# psu.net
KiCad netlist of a schematic drawn in EAGLE
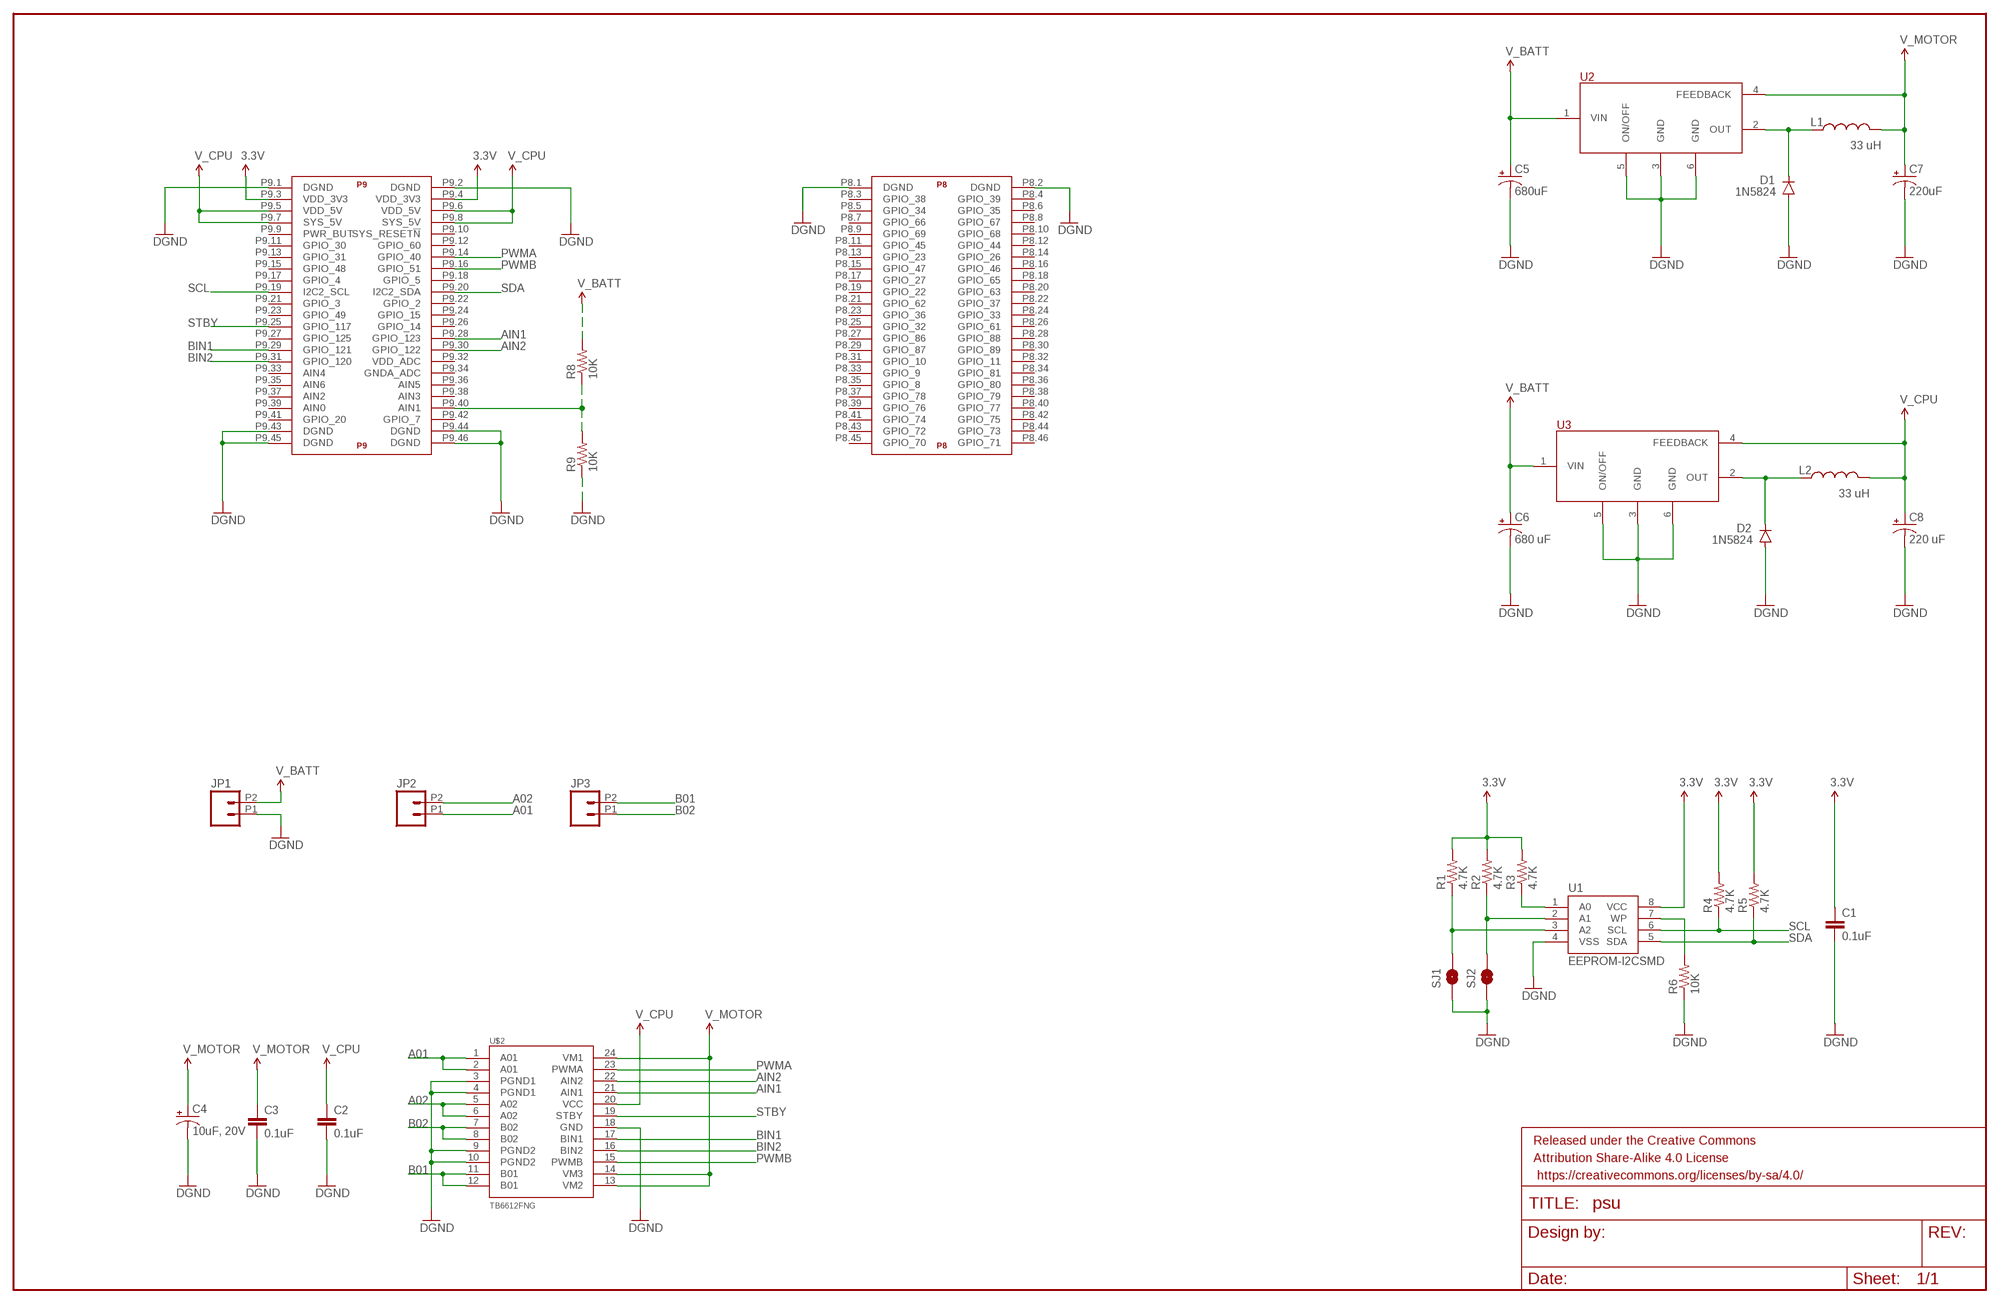
[diagram p0: schematic, sheet 1]

(export (version "E")
  (design (tool "Eeschema 10.0.6"))
  (components
    (comp (ref "C1")
      (value "0.1uF")
      (footprint "eagle-import:0603-CAP")
      (libsource (lib "eagle-import") (part "0.1UF-25V(+80/-20%)(0603)"))
    )
    (comp (ref "C2")
      (value "0.1uF")
      (footprint "eagle-import:0603-CAP")
      (libsource (lib "eagle-import") (part "0.1UF-25V(+80/-20%)(0603)"))
    )
    (comp (ref "C3")
      (value "0.1uF")
      (footprint "eagle-import:0603-CAP")
      (libsource (lib "eagle-import") (part "0.1UF-25V(+80/-20%)(0603)"))
    )
    (comp (ref "C4")
      (value "10uF, 20V")
      (footprint "eagle-import:CPOL-RADIAL-10UF-25V-KIT")
      (libsource (lib "eagle-import") (part "10UF-25V-20%(PTH)KIT"))
    )
    (comp (ref "C5")
      (value "680uF")
      (footprint "eagle-import:CPOL-RADIAL-10UF-25V")
      (libsource (lib "eagle-import") (part "CAP_POLPTH2"))
    )
    (comp (ref "C6")
      (value "680 uF")
      (footprint "eagle-import:CPOL-RADIAL-10UF-25V")
      (libsource (lib "eagle-import") (part "CAP_POLPTH2"))
    )
    (comp (ref "C7")
      (value "220uF")
      (footprint "eagle-import:CPOL-RADIAL-10UF-25V")
      (libsource (lib "eagle-import") (part "CAP_POLPTH2"))
    )
    (comp (ref "C8")
      (value "220 uF")
      (footprint "eagle-import:CPOL-RADIAL-10UF-25V")
      (libsource (lib "eagle-import") (part "CAP_POLPTH2"))
    )
    (comp (ref "D1")
      (value "1N5824")
      (footprint "eagle-import:DIODE-1N4001")
      (libsource (lib "eagle-import") (part "DIODEPTH"))
    )
    (comp (ref "D2")
      (value "1N5824")
      (footprint "eagle-import:DIODE-1N4001")
      (libsource (lib "eagle-import") (part "DIODEPTH"))
    )
    (comp (ref "FRAME2")
      (value "FRAME-LEDGER")
      (footprint "eagle-import:CREATIVE_COMMONS")
      (libsource (lib "eagle-import") (part "FRAME-LEDGER"))
    )
    (comp (ref "JP1")
      (value "M022.54MM_SCREWTERM")
      (footprint "eagle-import:1X02_2.54_SCREWTERM")
      (libsource (lib "eagle-import") (part "M022.54MM_SCREWTERM"))
    )
    (comp (ref "JP2")
      (value "M022.54MM_SCREWTERM")
      (footprint "eagle-import:1X02_2.54_SCREWTERM")
      (libsource (lib "eagle-import") (part "M022.54MM_SCREWTERM"))
    )
    (comp (ref "JP3")
      (value "M022.54MM_SCREWTERM")
      (footprint "eagle-import:1X02_2.54_SCREWTERM")
      (libsource (lib "eagle-import") (part "M022.54MM_SCREWTERM"))
    )
    (comp (ref "L1")
      (value "33 uH")
      (footprint "eagle-import:0603")
      (libsource (lib "eagle-import") (part "INDUCTOR0603"))
    )
    (comp (ref "L2")
      (value "33 uH")
      (footprint "eagle-import:0603")
      (libsource (lib "eagle-import") (part "INDUCTOR0603"))
    )
    (comp (ref "R1")
      (value "4.7K")
      (footprint "eagle-import:0603-RES")
      (libsource (lib "eagle-import") (part "4.7KOHM-1/10W-1%(0603)"))
    )
    (comp (ref "R2")
      (value "4.7K")
      (footprint "eagle-import:0603-RES")
      (libsource (lib "eagle-import") (part "4.7KOHM-1/10W-1%(0603)"))
    )
    (comp (ref "R3")
      (value "4.7K")
      (footprint "eagle-import:0603-RES")
      (libsource (lib "eagle-import") (part "4.7KOHM-1/10W-1%(0603)"))
    )
    (comp (ref "R4")
      (value "4.7K")
      (footprint "eagle-import:0603-RES")
      (libsource (lib "eagle-import") (part "4.7KOHM-1/10W-1%(0603)"))
    )
    (comp (ref "R5")
      (value "4.7K")
      (footprint "eagle-import:0603-RES")
      (libsource (lib "eagle-import") (part "4.7KOHM-1/10W-1%(0603)"))
    )
    (comp (ref "R6")
      (value "10K")
      (footprint "eagle-import:0603-RES")
      (libsource (lib "eagle-import") (part "10KOHM-1/10W-1%(0603)0603"))
    )
    (comp (ref "R8")
      (value "10K")
      (footprint "eagle-import:0603-RES")
      (libsource (lib "eagle-import") (part "10KOHM-1/10W-1%(0603)0603"))
    )
    (comp (ref "R9")
      (value "10K")
      (footprint "eagle-import:0603-RES")
      (libsource (lib "eagle-import") (part "10KOHM-1/10W-1%(0603)0603"))
    )
    (comp (ref "SJ1")
      (value "JUMPER-PAD-2-NO")
      (footprint "eagle-import:PAD-JUMPER-2-NO_NO_SILK")
      (libsource (lib "eagle-import") (part "JUMPER-PAD-2-NO"))
    )
    (comp (ref "SJ2")
      (value "JUMPER-PAD-2-NO")
      (footprint "eagle-import:PAD-JUMPER-2-NO_NO_SILK")
      (libsource (lib "eagle-import") (part "JUMPER-PAD-2-NO"))
    )
    (comp (ref "U$1")
      (value "BEAGLE_BONE_BLACK_CAPE")
      (footprint "eagle-import:BEAGLE_BONE_BLACK_CAPE")
      (libsource (lib "eagle-import") (part "BEAGLE_BONE_BLACK_CAPE"))
    )
    (comp (ref "U$2")
      (value "TB6612FNG")
      (footprint "eagle-import:SSOP24")
      (libsource (lib "eagle-import") (part "TB6612FNG"))
    )
    (comp (ref "U1")
      (value "EEPROM-I2CSMD")
      (footprint "eagle-import:SO08")
      (libsource (lib "eagle-import") (part "EEPROM-I2CSMD"))
    )
    (comp (ref "U2")
      (value "LM2596")
      (footprint "eagle-import:TO-263")
      (libsource (lib "eagle-import") (part "LM2596"))
    )
    (comp (ref "U3")
      (value "LM2596")
      (footprint "eagle-import:TO-263")
      (libsource (lib "eagle-import") (part "LM2596"))
    )
  )
  (nets
    (net (code "1") (name "/A01") (class "Default")
      (node (ref "JP2") (pin "P1") (pinfunction "1_P1") (pintype "passive"))
      (node (ref "U$2") (pin "1") (pinfunction "A01_1") (pintype "bidirectional"))
      (node (ref "U$2") (pin "2") (pinfunction "A01_2") (pintype "bidirectional"))
    )
    (net (code "2") (name "/A02") (class "Default")
      (node (ref "JP2") (pin "P2") (pinfunction "2_P2") (pintype "passive"))
      (node (ref "U$2") (pin "5") (pinfunction "A02_5") (pintype "bidirectional"))
      (node (ref "U$2") (pin "6") (pinfunction "A02_6") (pintype "bidirectional"))
    )
    (net (code "3") (name "/AIN1") (class "Default")
      (node (ref "U$1") (pin "P9.28") (pinfunction "GPIO_123_P9.28") (pintype "bidirectional"))
      (node (ref "U$2") (pin "21") (pinfunction "AIN1_21") (pintype "bidirectional"))
    )
    (net (code "4") (name "/AIN2") (class "Default")
      (node (ref "U$1") (pin "P9.30") (pinfunction "GPIO_122_P9.30") (pintype "bidirectional"))
      (node (ref "U$2") (pin "22") (pinfunction "AIN2_22") (pintype "bidirectional"))
    )
    (net (code "5") (name "/B01") (class "Default")
      (node (ref "JP3") (pin "P2") (pinfunction "2_P2") (pintype "passive"))
      (node (ref "U$2") (pin "11") (pinfunction "B01_11") (pintype "bidirectional"))
      (node (ref "U$2") (pin "12") (pinfunction "B01_12") (pintype "bidirectional"))
    )
    (net (code "6") (name "/B02") (class "Default")
      (node (ref "JP3") (pin "P1") (pinfunction "1_P1") (pintype "passive"))
      (node (ref "U$2") (pin "7") (pinfunction "B02_7") (pintype "bidirectional"))
      (node (ref "U$2") (pin "8") (pinfunction "B02_8") (pintype "bidirectional"))
    )
    (net (code "7") (name "/BIN1") (class "Default")
      (node (ref "U$1") (pin "P9.29") (pinfunction "GPIO_121_P9.29") (pintype "bidirectional"))
      (node (ref "U$2") (pin "17") (pinfunction "BIN1_17") (pintype "bidirectional"))
    )
    (net (code "8") (name "/BIN2") (class "Default")
      (node (ref "U$1") (pin "P9.31") (pinfunction "GPIO_120_P9.31") (pintype "bidirectional"))
      (node (ref "U$2") (pin "16") (pinfunction "BIN2_16") (pintype "bidirectional"))
    )
    (net (code "9") (name "/PWMA") (class "Default")
      (node (ref "U$1") (pin "P9.14") (pinfunction "GPIO_40_P9.14") (pintype "bidirectional"))
      (node (ref "U$2") (pin "23") (pinfunction "PWMA_23") (pintype "bidirectional"))
    )
    (net (code "10") (name "/PWMB") (class "Default")
      (node (ref "U$1") (pin "P9.16") (pinfunction "GPIO_51_P9.16") (pintype "bidirectional"))
      (node (ref "U$2") (pin "15") (pinfunction "PWMB_15") (pintype "bidirectional"))
    )
    (net (code "11") (name "/SCL") (class "Default")
      (node (ref "R4") (pin "1") (pinfunction "1_1") (pintype "passive"))
      (node (ref "U$1") (pin "P9.19") (pinfunction "I2C2_SCL_P9.19") (pintype "bidirectional"))
      (node (ref "U1") (pin "6") (pinfunction "SCL_6") (pintype "bidirectional"))
    )
    (net (code "12") (name "/SDA") (class "Default")
      (node (ref "R5") (pin "1") (pinfunction "1_1") (pintype "passive"))
      (node (ref "U$1") (pin "P9.20") (pinfunction "I2C2_SDA_P9.20") (pintype "bidirectional"))
      (node (ref "U1") (pin "5") (pinfunction "SDA_5") (pintype "bidirectional"))
    )
    (net (code "13") (name "/STBY") (class "Default")
      (node (ref "U$1") (pin "P9.25") (pinfunction "GPIO_117_P9.25") (pintype "bidirectional"))
      (node (ref "U$2") (pin "19") (pinfunction "STBY_19") (pintype "bidirectional"))
    )
    (net (code "14") (name "3.3V") (class "Default")
      (node (ref "C1") (pin "1") (pinfunction "1_1") (pintype "passive"))
      (node (ref "R1") (pin "2") (pinfunction "2_2") (pintype "passive"))
      (node (ref "R2") (pin "2") (pinfunction "2_2") (pintype "passive"))
      (node (ref "R3") (pin "2") (pinfunction "2_2") (pintype "passive"))
      (node (ref "R4") (pin "2") (pinfunction "2_2") (pintype "passive"))
      (node (ref "R5") (pin "2") (pinfunction "2_2") (pintype "passive"))
      (node (ref "U$1") (pin "P9.3") (pinfunction "VDD_3V3_P9.3") (pintype "bidirectional"))
      (node (ref "U$1") (pin "P9.4") (pinfunction "VDD_3V3_P9.4") (pintype "bidirectional"))
      (node (ref "U1") (pin "8") (pinfunction "VCC_8") (pintype "power_in"))
    )
    (net (code "15") (name "DGND") (class "Default")
      (node (ref "C1") (pin "2") (pinfunction "2_2") (pintype "passive"))
      (node (ref "C2") (pin "2") (pinfunction "2_2") (pintype "passive"))
      (node (ref "C3") (pin "2") (pinfunction "2_2") (pintype "passive"))
      (node (ref "C4") (pin "2") (pinfunction "-_2") (pintype "passive"))
      (node (ref "C5") (pin "2") (pinfunction "-_2") (pintype "passive"))
      (node (ref "C6") (pin "2") (pinfunction "-_2") (pintype "passive"))
      (node (ref "C7") (pin "2") (pinfunction "-_2") (pintype "passive"))
      (node (ref "C8") (pin "2") (pinfunction "-_2") (pintype "passive"))
      (node (ref "D1") (pin "A") (pinfunction "A_A") (pintype "passive"))
      (node (ref "D2") (pin "A") (pinfunction "A_A") (pintype "passive"))
      (node (ref "JP1") (pin "P1") (pinfunction "1_P1") (pintype "passive"))
      (node (ref "R6") (pin "1") (pinfunction "1_1") (pintype "passive"))
      (node (ref "R9") (pin "1") (pinfunction "1_1") (pintype "passive"))
      (node (ref "SJ1") (pin "1") (pinfunction "1_1") (pintype "passive"))
      (node (ref "SJ2") (pin "1") (pinfunction "1_1") (pintype "passive"))
      (node (ref "U$1") (pin "P8.1") (pinfunction "DGND_P8.1") (pintype "bidirectional"))
      (node (ref "U$1") (pin "P8.2") (pinfunction "DGND_P8.2") (pintype "bidirectional"))
      (node (ref "U$1") (pin "P9.1") (pinfunction "DGND_P9.1") (pintype "bidirectional"))
      (node (ref "U$1") (pin "P9.2") (pinfunction "DGND_P9.2") (pintype "bidirectional"))
      (node (ref "U$1") (pin "P9.43") (pinfunction "DGND_P9.43") (pintype "bidirectional"))
      (node (ref "U$1") (pin "P9.44") (pinfunction "DGND_P9.44") (pintype "bidirectional"))
      (node (ref "U$1") (pin "P9.45") (pinfunction "DGND_P9.45") (pintype "bidirectional"))
      (node (ref "U$1") (pin "P9.46") (pinfunction "DGND_P9.46") (pintype "bidirectional"))
      (node (ref "U$2") (pin "10") (pinfunction "PGND2_10") (pintype "bidirectional"))
      (node (ref "U$2") (pin "18") (pinfunction "GND_18") (pintype "bidirectional"))
      (node (ref "U$2") (pin "3") (pinfunction "PGND1_3") (pintype "bidirectional"))
      (node (ref "U$2") (pin "4") (pinfunction "PGND1_4") (pintype "bidirectional"))
      (node (ref "U$2") (pin "9") (pinfunction "PGND2_9") (pintype "bidirectional"))
      (node (ref "U1") (pin "4") (pinfunction "VSS_4") (pintype "power_in"))
      (node (ref "U2") (pin "3") (pinfunction "GND_3") (pintype "power_in"))
      (node (ref "U2") (pin "5") (pinfunction "ON/OFF_5") (pintype "input"))
      (node (ref "U2") (pin "6") (pinfunction "GND_6") (pintype "power_in"))
      (node (ref "U3") (pin "3") (pinfunction "GND_3") (pintype "power_in"))
      (node (ref "U3") (pin "5") (pinfunction "ON/OFF_5") (pintype "input"))
      (node (ref "U3") (pin "6") (pinfunction "GND_6") (pintype "power_in"))
    )
    (net (code "16") (name "Net-(U$1B-AIN1)") (class "Default")
      (node (ref "R8") (pin "1") (pinfunction "1_1") (pintype "passive"))
      (node (ref "R9") (pin "2") (pinfunction "2_2") (pintype "passive"))
      (node (ref "U$1") (pin "P9.40") (pinfunction "AIN1_P9.40") (pintype "bidirectional"))
    )
    (net (code "17") (name "Net-(U1-A0)") (class "Default")
      (node (ref "R3") (pin "1") (pinfunction "1_1") (pintype "passive"))
      (node (ref "U1") (pin "1") (pinfunction "A0_1") (pintype "bidirectional"))
    )
    (net (code "18") (name "Net-(U1-A1)") (class "Default")
      (node (ref "R2") (pin "1") (pinfunction "1_1") (pintype "passive"))
      (node (ref "SJ2") (pin "2") (pinfunction "2_2") (pintype "passive"))
      (node (ref "U1") (pin "2") (pinfunction "A1_2") (pintype "bidirectional"))
    )
    (net (code "19") (name "Net-(U1-A2)") (class "Default")
      (node (ref "R1") (pin "1") (pinfunction "1_1") (pintype "passive"))
      (node (ref "SJ1") (pin "2") (pinfunction "2_2") (pintype "passive"))
      (node (ref "U1") (pin "3") (pinfunction "A2_3") (pintype "bidirectional"))
    )
    (net (code "20") (name "Net-(U1-WP)") (class "Default")
      (node (ref "R6") (pin "2") (pinfunction "2_2") (pintype "passive"))
      (node (ref "U1") (pin "7") (pinfunction "WP_7") (pintype "bidirectional"))
    )
    (net (code "21") (name "Net-(U2-OUT)") (class "Default")
      (node (ref "D1") (pin "C") (pinfunction "C_C") (pintype "passive"))
      (node (ref "L1") (pin "1") (pinfunction "1_1") (pintype "passive"))
      (node (ref "U2") (pin "2") (pinfunction "OUT_2") (pintype "power_in"))
    )
    (net (code "22") (name "Net-(U3-OUT)") (class "Default")
      (node (ref "D2") (pin "C") (pinfunction "C_C") (pintype "passive"))
      (node (ref "L2") (pin "1") (pinfunction "1_1") (pintype "passive"))
      (node (ref "U3") (pin "2") (pinfunction "OUT_2") (pintype "power_in"))
    )
    (net (code "23") (name "V_BATT") (class "Default")
      (node (ref "C5") (pin "1") (pinfunction "+_1") (pintype "passive"))
      (node (ref "C6") (pin "1") (pinfunction "+_1") (pintype "passive"))
      (node (ref "JP1") (pin "P2") (pinfunction "2_P2") (pintype "passive"))
      (node (ref "R8") (pin "2") (pinfunction "2_2") (pintype "passive"))
      (node (ref "U2") (pin "1") (pinfunction "VIN_1") (pintype "power_in"))
      (node (ref "U3") (pin "1") (pinfunction "VIN_1") (pintype "power_in"))
    )
    (net (code "24") (name "V_CPU") (class "Default")
      (node (ref "C2") (pin "1") (pinfunction "1_1") (pintype "passive"))
      (node (ref "C8") (pin "1") (pinfunction "+_1") (pintype "passive"))
      (node (ref "L2") (pin "2") (pinfunction "2_2") (pintype "passive"))
      (node (ref "U$1") (pin "P9.5") (pinfunction "VDD_5V_P9.5") (pintype "bidirectional"))
      (node (ref "U$1") (pin "P9.6") (pinfunction "VDD_5V_P9.6") (pintype "bidirectional"))
      (node (ref "U$1") (pin "P9.7") (pinfunction "SYS_5V_P9.7") (pintype "bidirectional"))
      (node (ref "U$1") (pin "P9.8") (pinfunction "SYS_5V_P9.8") (pintype "bidirectional"))
      (node (ref "U$2") (pin "20") (pinfunction "VCC_20") (pintype "bidirectional"))
      (node (ref "U3") (pin "4") (pinfunction "FEEDBACK_4") (pintype "output"))
    )
    (net (code "25") (name "V_MOTOR") (class "Default")
      (node (ref "C3") (pin "1") (pinfunction "1_1") (pintype "passive"))
      (node (ref "C4") (pin "1") (pinfunction "+_1") (pintype "passive"))
      (node (ref "C7") (pin "1") (pinfunction "+_1") (pintype "passive"))
      (node (ref "L1") (pin "2") (pinfunction "2_2") (pintype "passive"))
      (node (ref "U$2") (pin "13") (pinfunction "VM2_13") (pintype "bidirectional"))
      (node (ref "U$2") (pin "14") (pinfunction "VM3_14") (pintype "bidirectional"))
      (node (ref "U$2") (pin "24") (pinfunction "VM1_24") (pintype "bidirectional"))
      (node (ref "U2") (pin "4") (pinfunction "FEEDBACK_4") (pintype "output"))
    )
    (net (code "26") (name "unconnected-(U$1A-GPIO_8-PadP8.35)") (class "Default")
      (node (ref "U$1") (pin "P8.35") (pinfunction "GPIO_8_P8.35") (pintype "bidirectional"))
    )
    (net (code "27") (name "unconnected-(U$1A-GPIO_9-PadP8.33)") (class "Default")
      (node (ref "U$1") (pin "P8.33") (pinfunction "GPIO_9_P8.33") (pintype "bidirectional"))
    )
    (net (code "28") (name "unconnected-(U$1A-GPIO_10-PadP8.31)") (class "Default")
      (node (ref "U$1") (pin "P8.31") (pinfunction "GPIO_10_P8.31") (pintype "bidirectional"))
    )
    (net (code "29") (name "unconnected-(U$1A-GPIO_11-PadP8.32)") (class "Default")
      (node (ref "U$1") (pin "P8.32") (pinfunction "GPIO_11_P8.32") (pintype "bidirectional"))
    )
    (net (code "30") (name "unconnected-(U$1A-GPIO_22-PadP8.19)") (class "Default")
      (node (ref "U$1") (pin "P8.19") (pinfunction "GPIO_22_P8.19") (pintype "bidirectional"))
    )
    (net (code "31") (name "unconnected-(U$1A-GPIO_23-PadP8.13)") (class "Default")
      (node (ref "U$1") (pin "P8.13") (pinfunction "GPIO_23_P8.13") (pintype "bidirectional"))
    )
    (net (code "32") (name "unconnected-(U$1A-GPIO_26-PadP8.14)") (class "Default")
      (node (ref "U$1") (pin "P8.14") (pinfunction "GPIO_26_P8.14") (pintype "bidirectional"))
    )
    (net (code "33") (name "unconnected-(U$1A-GPIO_27-PadP8.17)") (class "Default")
      (node (ref "U$1") (pin "P8.17") (pinfunction "GPIO_27_P8.17") (pintype "bidirectional"))
    )
    (net (code "34") (name "unconnected-(U$1A-GPIO_32-PadP8.25)") (class "Default")
      (node (ref "U$1") (pin "P8.25") (pinfunction "GPIO_32_P8.25") (pintype "bidirectional"))
    )
    (net (code "35") (name "unconnected-(U$1A-GPIO_33-PadP8.24)") (class "Default")
      (node (ref "U$1") (pin "P8.24") (pinfunction "GPIO_33_P8.24") (pintype "bidirectional"))
    )
    (net (code "36") (name "unconnected-(U$1A-GPIO_34-PadP8.5)") (class "Default")
      (node (ref "U$1") (pin "P8.5") (pinfunction "GPIO_34_P8.5") (pintype "bidirectional"))
    )
    (net (code "37") (name "unconnected-(U$1A-GPIO_35-PadP8.6)") (class "Default")
      (node (ref "U$1") (pin "P8.6") (pinfunction "GPIO_35_P8.6") (pintype "bidirectional"))
    )
    (net (code "38") (name "unconnected-(U$1A-GPIO_36-PadP8.23)") (class "Default")
      (node (ref "U$1") (pin "P8.23") (pinfunction "GPIO_36_P8.23") (pintype "bidirectional"))
    )
    (net (code "39") (name "unconnected-(U$1A-GPIO_37-PadP8.22)") (class "Default")
      (node (ref "U$1") (pin "P8.22") (pinfunction "GPIO_37_P8.22") (pintype "bidirectional"))
    )
    (net (code "40") (name "unconnected-(U$1A-GPIO_38-PadP8.3)") (class "Default")
      (node (ref "U$1") (pin "P8.3") (pinfunction "GPIO_38_P8.3") (pintype "bidirectional"))
    )
    (net (code "41") (name "unconnected-(U$1A-GPIO_39-PadP8.4)") (class "Default")
      (node (ref "U$1") (pin "P8.4") (pinfunction "GPIO_39_P8.4") (pintype "bidirectional"))
    )
    (net (code "42") (name "unconnected-(U$1A-GPIO_44-PadP8.12)") (class "Default")
      (node (ref "U$1") (pin "P8.12") (pinfunction "GPIO_44_P8.12") (pintype "bidirectional"))
    )
    (net (code "43") (name "unconnected-(U$1A-GPIO_45-PadP8.11)") (class "Default")
      (node (ref "U$1") (pin "P8.11") (pinfunction "GPIO_45_P8.11") (pintype "bidirectional"))
    )
    (net (code "44") (name "unconnected-(U$1A-GPIO_46-PadP8.16)") (class "Default")
      (node (ref "U$1") (pin "P8.16") (pinfunction "GPIO_46_P8.16") (pintype "bidirectional"))
    )
    (net (code "45") (name "unconnected-(U$1A-GPIO_47-PadP8.15)") (class "Default")
      (node (ref "U$1") (pin "P8.15") (pinfunction "GPIO_47_P8.15") (pintype "bidirectional"))
    )
    (net (code "46") (name "unconnected-(U$1A-GPIO_61-PadP8.26)") (class "Default")
      (node (ref "U$1") (pin "P8.26") (pinfunction "GPIO_61_P8.26") (pintype "bidirectional"))
    )
    (net (code "47") (name "unconnected-(U$1A-GPIO_62-PadP8.21)") (class "Default")
      (node (ref "U$1") (pin "P8.21") (pinfunction "GPIO_62_P8.21") (pintype "bidirectional"))
    )
    (net (code "48") (name "unconnected-(U$1A-GPIO_63-PadP8.20)") (class "Default")
      (node (ref "U$1") (pin "P8.20") (pinfunction "GPIO_63_P8.20") (pintype "bidirectional"))
    )
    (net (code "49") (name "unconnected-(U$1A-GPIO_65-PadP8.18)") (class "Default")
      (node (ref "U$1") (pin "P8.18") (pinfunction "GPIO_65_P8.18") (pintype "bidirectional"))
    )
    (net (code "50") (name "unconnected-(U$1A-GPIO_66-PadP8.7)") (class "Default")
      (node (ref "U$1") (pin "P8.7") (pinfunction "GPIO_66_P8.7") (pintype "bidirectional"))
    )
    (net (code "51") (name "unconnected-(U$1A-GPIO_67-PadP8.8)") (class "Default")
      (node (ref "U$1") (pin "P8.8") (pinfunction "GPIO_67_P8.8") (pintype "bidirectional"))
    )
    (net (code "52") (name "unconnected-(U$1A-GPIO_68-PadP8.10)") (class "Default")
      (node (ref "U$1") (pin "P8.10") (pinfunction "GPIO_68_P8.10") (pintype "bidirectional"))
    )
    (net (code "53") (name "unconnected-(U$1A-GPIO_69-PadP8.9)") (class "Default")
      (node (ref "U$1") (pin "P8.9") (pinfunction "GPIO_69_P8.9") (pintype "bidirectional"))
    )
    (net (code "54") (name "unconnected-(U$1A-GPIO_70-PadP8.45)") (class "Default")
      (node (ref "U$1") (pin "P8.45") (pinfunction "GPIO_70_P8.45") (pintype "bidirectional"))
    )
    (net (code "55") (name "unconnected-(U$1A-GPIO_71-PadP8.46)") (class "Default")
      (node (ref "U$1") (pin "P8.46") (pinfunction "GPIO_71_P8.46") (pintype "bidirectional"))
    )
    (net (code "56") (name "unconnected-(U$1A-GPIO_72-PadP8.43)") (class "Default")
      (node (ref "U$1") (pin "P8.43") (pinfunction "GPIO_72_P8.43") (pintype "bidirectional"))
    )
    (net (code "57") (name "unconnected-(U$1A-GPIO_73-PadP8.44)") (class "Default")
      (node (ref "U$1") (pin "P8.44") (pinfunction "GPIO_73_P8.44") (pintype "bidirectional"))
    )
    (net (code "58") (name "unconnected-(U$1A-GPIO_74-PadP8.41)") (class "Default")
      (node (ref "U$1") (pin "P8.41") (pinfunction "GPIO_74_P8.41") (pintype "bidirectional"))
    )
    (net (code "59") (name "unconnected-(U$1A-GPIO_75-PadP8.42)") (class "Default")
      (node (ref "U$1") (pin "P8.42") (pinfunction "GPIO_75_P8.42") (pintype "bidirectional"))
    )
    (net (code "60") (name "unconnected-(U$1A-GPIO_76-PadP8.39)") (class "Default")
      (node (ref "U$1") (pin "P8.39") (pinfunction "GPIO_76_P8.39") (pintype "bidirectional"))
    )
    (net (code "61") (name "unconnected-(U$1A-GPIO_77-PadP8.40)") (class "Default")
      (node (ref "U$1") (pin "P8.40") (pinfunction "GPIO_77_P8.40") (pintype "bidirectional"))
    )
    (net (code "62") (name "unconnected-(U$1A-GPIO_78-PadP8.37)") (class "Default")
      (node (ref "U$1") (pin "P8.37") (pinfunction "GPIO_78_P8.37") (pintype "bidirectional"))
    )
    (net (code "63") (name "unconnected-(U$1A-GPIO_79-PadP8.38)") (class "Default")
      (node (ref "U$1") (pin "P8.38") (pinfunction "GPIO_79_P8.38") (pintype "bidirectional"))
    )
    (net (code "64") (name "unconnected-(U$1A-GPIO_80-PadP8.36)") (class "Default")
      (node (ref "U$1") (pin "P8.36") (pinfunction "GPIO_80_P8.36") (pintype "bidirectional"))
    )
    (net (code "65") (name "unconnected-(U$1A-GPIO_81-PadP8.34)") (class "Default")
      (node (ref "U$1") (pin "P8.34") (pinfunction "GPIO_81_P8.34") (pintype "bidirectional"))
    )
    (net (code "66") (name "unconnected-(U$1A-GPIO_86-PadP8.27)") (class "Default")
      (node (ref "U$1") (pin "P8.27") (pinfunction "GPIO_86_P8.27") (pintype "bidirectional"))
    )
    (net (code "67") (name "unconnected-(U$1A-GPIO_87-PadP8.29)") (class "Default")
      (node (ref "U$1") (pin "P8.29") (pinfunction "GPIO_87_P8.29") (pintype "bidirectional"))
    )
    (net (code "68") (name "unconnected-(U$1A-GPIO_88-PadP8.28)") (class "Default")
      (node (ref "U$1") (pin "P8.28") (pinfunction "GPIO_88_P8.28") (pintype "bidirectional"))
    )
    (net (code "69") (name "unconnected-(U$1A-GPIO_89-PadP8.30)") (class "Default")
      (node (ref "U$1") (pin "P8.30") (pinfunction "GPIO_89_P8.30") (pintype "bidirectional"))
    )
    (net (code "70") (name "unconnected-(U$1B-AIN0-PadP9.39)") (class "Default")
      (node (ref "U$1") (pin "P9.39") (pinfunction "AIN0_P9.39") (pintype "bidirectional"))
    )
    (net (code "71") (name "unconnected-(U$1B-AIN2-PadP9.37)") (class "Default")
      (node (ref "U$1") (pin "P9.37") (pinfunction "AIN2_P9.37") (pintype "bidirectional"))
    )
    (net (code "72") (name "unconnected-(U$1B-AIN3-PadP9.38)") (class "Default")
      (node (ref "U$1") (pin "P9.38") (pinfunction "AIN3_P9.38") (pintype "bidirectional"))
    )
    (net (code "73") (name "unconnected-(U$1B-AIN4-PadP9.33)") (class "Default")
      (node (ref "U$1") (pin "P9.33") (pinfunction "AIN4_P9.33") (pintype "bidirectional"))
    )
    (net (code "74") (name "unconnected-(U$1B-AIN5-PadP9.36)") (class "Default")
      (node (ref "U$1") (pin "P9.36") (pinfunction "AIN5_P9.36") (pintype "bidirectional"))
    )
    (net (code "75") (name "unconnected-(U$1B-AIN6-PadP9.35)") (class "Default")
      (node (ref "U$1") (pin "P9.35") (pinfunction "AIN6_P9.35") (pintype "bidirectional"))
    )
    (net (code "76") (name "unconnected-(U$1B-GNDA_ADC-PadP9.34)") (class "Default")
      (node (ref "U$1") (pin "P9.34") (pinfunction "GNDA_ADC_P9.34") (pintype "bidirectional"))
    )
    (net (code "77") (name "unconnected-(U$1B-GPIO_2-PadP9.22)") (class "Default")
      (node (ref "U$1") (pin "P9.22") (pinfunction "GPIO_2_P9.22") (pintype "bidirectional"))
    )
    (net (code "78") (name "unconnected-(U$1B-GPIO_3-PadP9.21)") (class "Default")
      (node (ref "U$1") (pin "P9.21") (pinfunction "GPIO_3_P9.21") (pintype "bidirectional"))
    )
    (net (code "79") (name "unconnected-(U$1B-GPIO_4-PadP9.17)") (class "Default")
      (node (ref "U$1") (pin "P9.17") (pinfunction "GPIO_4_P9.17") (pintype "bidirectional"))
    )
    (net (code "80") (name "unconnected-(U$1B-GPIO_5-PadP9.18)") (class "Default")
      (node (ref "U$1") (pin "P9.18") (pinfunction "GPIO_5_P9.18") (pintype "bidirectional"))
    )
    (net (code "81") (name "unconnected-(U$1B-GPIO_7-PadP9.42)") (class "Default")
      (node (ref "U$1") (pin "P9.42") (pinfunction "GPIO_7_P9.42") (pintype "bidirectional"))
    )
    (net (code "82") (name "unconnected-(U$1B-GPIO_14-PadP9.26)") (class "Default")
      (node (ref "U$1") (pin "P9.26") (pinfunction "GPIO_14_P9.26") (pintype "bidirectional"))
    )
    (net (code "83") (name "unconnected-(U$1B-GPIO_15-PadP9.24)") (class "Default")
      (node (ref "U$1") (pin "P9.24") (pinfunction "GPIO_15_P9.24") (pintype "bidirectional"))
    )
    (net (code "84") (name "unconnected-(U$1B-GPIO_20-PadP9.41)") (class "Default")
      (node (ref "U$1") (pin "P9.41") (pinfunction "GPIO_20_P9.41") (pintype "bidirectional"))
    )
    (net (code "85") (name "unconnected-(U$1B-GPIO_30-PadP9.11)") (class "Default")
      (node (ref "U$1") (pin "P9.11") (pinfunction "GPIO_30_P9.11") (pintype "bidirectional"))
    )
    (net (code "86") (name "unconnected-(U$1B-GPIO_31-PadP9.13)") (class "Default")
      (node (ref "U$1") (pin "P9.13") (pinfunction "GPIO_31_P9.13") (pintype "bidirectional"))
    )
    (net (code "87") (name "unconnected-(U$1B-GPIO_48-PadP9.15)") (class "Default")
      (node (ref "U$1") (pin "P9.15") (pinfunction "GPIO_48_P9.15") (pintype "bidirectional"))
    )
    (net (code "88") (name "unconnected-(U$1B-GPIO_49-PadP9.23)") (class "Default")
      (node (ref "U$1") (pin "P9.23") (pinfunction "GPIO_49_P9.23") (pintype "bidirectional"))
    )
    (net (code "89") (name "unconnected-(U$1B-GPIO_60-PadP9.12)") (class "Default")
      (node (ref "U$1") (pin "P9.12") (pinfunction "GPIO_60_P9.12") (pintype "bidirectional"))
    )
    (net (code "90") (name "unconnected-(U$1B-GPIO_125-PadP9.27)") (class "Default")
      (node (ref "U$1") (pin "P9.27") (pinfunction "GPIO_125_P9.27") (pintype "bidirectional"))
    )
    (net (code "91") (name "unconnected-(U$1B-PWR_BUT-PadP9.9)") (class "Default")
      (node (ref "U$1") (pin "P9.9") (pinfunction "PWR_BUT_P9.9") (pintype "bidirectional"))
    )
    (net (code "92") (name "unconnected-(U$1B-SYS_RESET~{N}-PadP9.10)") (class "Default")
      (node (ref "U$1") (pin "P9.10") (pinfunction "SYS_RESET~{N}_P9.10") (pintype "bidirectional"))
    )
    (net (code "93") (name "unconnected-(U$1B-VDD_ADC-PadP9.32)") (class "Default")
      (node (ref "U$1") (pin "P9.32") (pinfunction "VDD_ADC_P9.32") (pintype "bidirectional"))
    )
  )
)
